# UBC-Thunderbots_PCB_Power__archive_power.net
KiCad netlist of a schematic drawn in Altium Designer
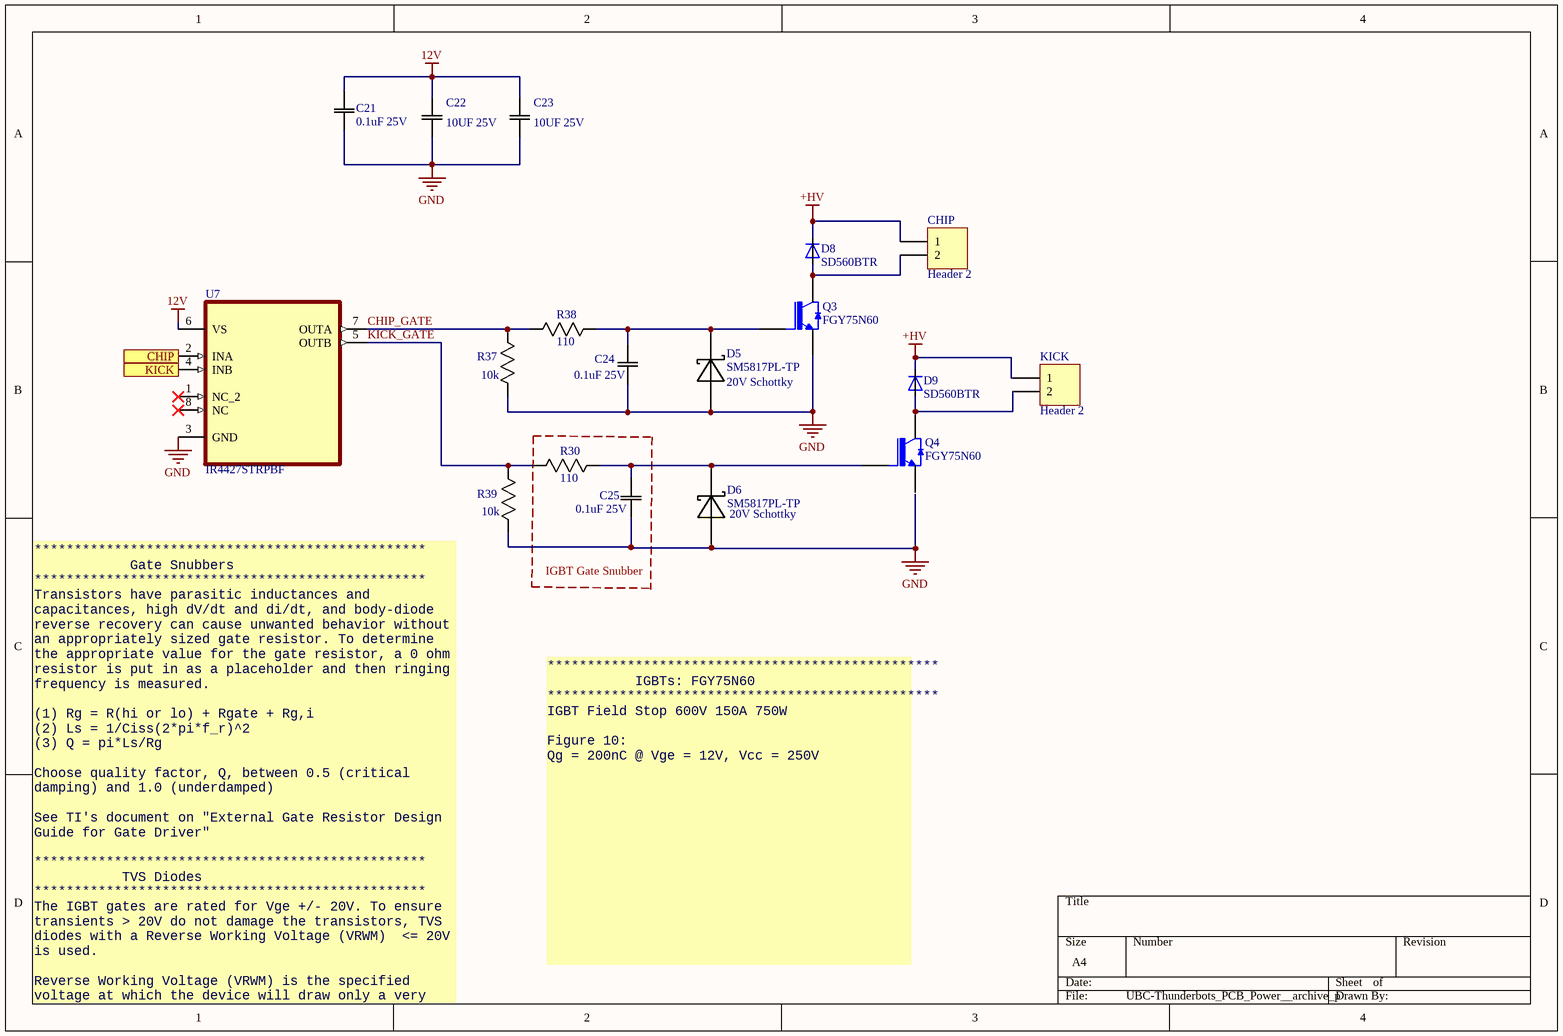
[diagram p0: UBC-Thunderbots_PCB_Power__archive_power-v2.2_pcb__chicker.SchDoc]

(export (version "E")
  (design (tool "Eeschema 10.0.6"))
  (components
    (comp (ref "C21")
      (value "0.1uF 25V")
      (footprint "0805")
      (description "CAP CER 0.1UF 25V X7R 0805")
      (fields (field (name "TOLERANCE") "10%"))
      (libsource (lib "") (part "CAP 0.1uF 25V_1"))
    )
    (comp (ref "C22")
      (value "10UF 25V")
      (footprint "1206")
      (description "CAP CER 10UF 25V X5R 1206")
      (fields (field (name "TOLERANCE") "10%"))
      (libsource (lib "AltiumLibraries") (part "CAP 10uF 25V"))
    )
    (comp (ref "C23")
      (value "10UF 25V")
      (footprint "1206")
      (description "CAP CER 10UF 25V X5R 1206")
      (fields (field (name "TOLERANCE") "10%"))
      (libsource (lib "AltiumLibraries") (part "CAP 10uF 25V"))
    )
    (comp (ref "C24")
      (value "0.1uF 25V")
      (footprint "0805")
      (description "CAP CER 0.1UF 25V X7R 0805")
      (fields (field (name "TOLERANCE") "10%"))
      (libsource (lib "AltiumLibraries") (part "CAP 0.1uF 25V"))
    )
    (comp (ref "C25")
      (value "0.1uF 25V")
      (footprint "0805")
      (description "CAP CER 0.1UF 25V X7R 0805")
      (fields (field (name "TOLERANCE") "10%"))
      (libsource (lib "AltiumLibraries") (part "CAP 0.1uF 25V"))
    )
    (comp (ref "CHIP")
      (value "Header 2")
      (footprint "HDR1X2")
      (description "Header, 2-Pin")
      (fields (field (name "PUBLISHER") "Altium Limited"))
      (libsource (lib "Miscellaneous Connectors") (part "Header 2"))
    )
    (comp (ref "D5")
      (value "SM5817PL-TP")
      (footprint "SOD-123")
      (description "Diode Schottky 20V 1A Surface Mount SOD-123FL")
      (fields (field (name "MF") "Micro Commercial Co"))
      (libsource (lib "AltiumLibraries") (part "SM5817PL-TP"))
    )
    (comp (ref "D6")
      (value "SM5817PL-TP")
      (footprint "SOD-123")
      (description "Diode Schottky 20V 1A Surface Mount SOD-123FL")
      (fields (field (name "MF") "Micro Commercial Co"))
      (libsource (lib "AltiumLibraries") (part "SM5817PL-TP"))
    )
    (comp (ref "D8")
      (value "SD560BTR")
      (footprint "DO-214AA")
      (description "Diode Standard 600V 5A Surface Mount SMB")
      (libsource (lib "AltiumLibraries") (part "SD560BTR"))
    )
    (comp (ref "D9")
      (value "SD560BTR")
      (footprint "DO-214AA")
      (description "Diode Standard 600V 5A Surface Mount SMB")
      (libsource (lib "AltiumLibraries") (part "SD560BTR"))
    )
    (comp (ref "KICK")
      (value "Header 2")
      (footprint "HDR1X2")
      (description "Header, 2-Pin")
      (fields (field (name "PUBLISHER") "Altium Limited"))
      (libsource (lib "Miscellaneous Connectors") (part "Header 2"))
    )
    (comp (ref "Q3")
      (value "FGY75N60")
      (footprint "TO-247-3")
      (description "IGBT Field Stop 600V 150A 750W Through Hole PowerTO-247-3")
      (fields (field (name "MF") "ON Semiconductor") (field (name "MP") "FGY75N60SMD"))
      (libsource (lib "AltiumLibraries") (part "FGY75N60SMD"))
    )
    (comp (ref "Q4")
      (value "FGY75N60")
      (footprint "TO-247-3")
      (description "IGBT Field Stop 600V 150A 750W Through Hole PowerTO-247-3")
      (fields (field (name "MF") "ON Semiconductor") (field (name "MP") "FGY75N60SMD"))
      (libsource (lib "AltiumLibraries") (part "FGY75N60SMD"))
    )
    (comp (ref "R30")
      (value "110")
      (footprint "0805")
      (description "RES SMD 110 OHM 1% 1/8W 0805")
      (fields (field (name "TOLERANCE") "1%"))
      (libsource (lib "AltiumLibraries") (part "RES 110 1/8W"))
    )
    (comp (ref "R37")
      (value "10k")
      (footprint "0805")
      (description "RES SMD 10K OHM 1% 1/8W 0805")
      (fields (field (name "TOLERANCE") "1%"))
      (libsource (lib "AltiumLibraries") (part "RES 10k 1/8W"))
    )
    (comp (ref "R38")
      (value "110")
      (footprint "0805")
      (description "RES SMD 110 OHM 1% 1/8W 0805")
      (fields (field (name "TOLERANCE") "1%"))
      (libsource (lib "") (part "RES 110 1/8W_1"))
    )
    (comp (ref "R39")
      (value "10k")
      (footprint "0805")
      (description "RES SMD 10K OHM 1% 1/8W 0805")
      (fields (field (name "TOLERANCE") "1%"))
      (libsource (lib "AltiumLibraries") (part "RES 10k 1/8W"))
    )
    (comp (ref "U7")
      (value "IR4427STRPBF")
      (footprint "8-SOIC")
      (description "Low-Side Gate Driver IC Non-Inverting 8-SOIC")
      (fields (field (name "MF") "Infineon Technologies"))
      (libsource (lib "AltiumLibraries") (part "IR4427STRPBF"))
    )
  )
  (nets
    (net (code "1") (name "+HV") (class "Default")
      (node (ref "CHIP") (pin "1") (pinfunction "1_1") (pintype "passive"))
      (node (ref "D8") (pin "C") (pinfunction "C_C") (pintype "passive"))
      (node (ref "D9") (pin "C") (pinfunction "C_C") (pintype "passive"))
      (node (ref "KICK") (pin "1") (pinfunction "1_1") (pintype "passive"))
    )
    (net (code "2") (name "/CHIP") (class "Default")
      (node (ref "U7") (pin "2") (pinfunction "INA_2") (pintype "input"))
    )
    (net (code "3") (name "/CHIP_GATE") (class "Default")
      (node (ref "R37") (pin "1") (pinfunction "R1_1") (pintype "passive"))
      (node (ref "R38") (pin "2") (pinfunction "R2_2") (pintype "passive"))
      (node (ref "U7") (pin "7") (pinfunction "OUTA_7") (pintype "output"))
    )
    (net (code "4") (name "/KICK") (class "Default")
      (node (ref "U7") (pin "4") (pinfunction "INB_4") (pintype "input"))
    )
    (net (code "5") (name "/KICK_GATE") (class "Default")
      (node (ref "R30") (pin "2") (pinfunction "R2_2") (pintype "passive"))
      (node (ref "R39") (pin "1") (pinfunction "R1_1") (pintype "passive"))
      (node (ref "U7") (pin "5") (pinfunction "OUTB_5") (pintype "output"))
    )
    (net (code "6") (name "12V") (class "Default")
      (node (ref "C21") (pin "2") (pinfunction "C2_2") (pintype "passive"))
      (node (ref "C22") (pin "1") (pinfunction "C1_1") (pintype "passive"))
      (node (ref "C23") (pin "1") (pinfunction "C1_1") (pintype "passive"))
      (node (ref "U7") (pin "6") (pinfunction "VS_6") (pintype "power_in"))
    )
    (net (code "7") (name "GND") (class "Default")
      (node (ref "C21") (pin "1") (pinfunction "C1_1") (pintype "passive"))
      (node (ref "C22") (pin "2") (pinfunction "C2_2") (pintype "passive"))
      (node (ref "C23") (pin "2") (pinfunction "C2_2") (pintype "passive"))
      (node (ref "C24") (pin "1") (pinfunction "C1_1") (pintype "passive"))
      (node (ref "C25") (pin "1") (pinfunction "C1_1") (pintype "passive"))
      (node (ref "D5") (pin "A") (pinfunction "A_A") (pintype "passive"))
      (node (ref "D6") (pin "A") (pinfunction "A_A") (pintype "passive"))
      (node (ref "Q3") (pin "3") (pinfunction "E_3") (pintype "passive"))
      (node (ref "R37") (pin "2") (pinfunction "R2_2") (pintype "passive"))
      (node (ref "R39") (pin "2") (pinfunction "R2_2") (pintype "passive"))
      (node (ref "U7") (pin "3") (pinfunction "GND_3") (pintype "passive"))
    )
    (net (code "8") (name "Net-(C24-C2)") (class "Default")
      (node (ref "C24") (pin "2") (pinfunction "C2_2") (pintype "passive"))
      (node (ref "D5") (pin "C") (pinfunction "K_C") (pintype "passive"))
      (node (ref "Q3") (pin "1") (pinfunction "G_1") (pintype "passive"))
      (node (ref "R38") (pin "1") (pinfunction "R1_1") (pintype "passive"))
    )
    (net (code "9") (name "Net-(C25-C2)") (class "Default")
      (node (ref "C25") (pin "2") (pinfunction "C2_2") (pintype "passive"))
      (node (ref "D6") (pin "C") (pinfunction "K_C") (pintype "passive"))
      (node (ref "Q4") (pin "1") (pinfunction "G_1") (pintype "passive"))
      (node (ref "R30") (pin "1") (pinfunction "R1_1") (pintype "passive"))
    )
    (net (code "10") (name "Net-(Q3-C)") (class "Default")
      (node (ref "CHIP") (pin "2") (pinfunction "2_2") (pintype "passive"))
      (node (ref "D8") (pin "A") (pinfunction "A_A") (pintype "passive"))
      (node (ref "Q3") (pin "2") (pinfunction "C_2") (pintype "passive"))
    )
    (net (code "11") (name "Net-(Q4-C)") (class "Default")
      (node (ref "D9") (pin "A") (pinfunction "A_A") (pintype "passive"))
      (node (ref "KICK") (pin "2") (pinfunction "2_2") (pintype "passive"))
      (node (ref "Q4") (pin "2") (pinfunction "C_2") (pintype "passive"))
    )
    (net (code "12") (name "unconnected-(Q4-E-Pad3)") (class "Default")
      (node (ref "Q4") (pin "3") (pinfunction "E_3") (pintype "passive"))
    )
    (net (code "13") (name "unconnected-(U7-NC-Pad8)") (class "Default")
      (node (ref "U7") (pin "8") (pinfunction "NC_8") (pintype "input+no_connect"))
    )
    (net (code "14") (name "unconnected-(U7-NC_2-Pad1)") (class "Default")
      (node (ref "U7") (pin "1") (pinfunction "NC_2_1") (pintype "input+no_connect"))
    )
  )
)
